# 05_RK3128_VDD.net
KiCad netlist of a schematic drawn in Altium Designer
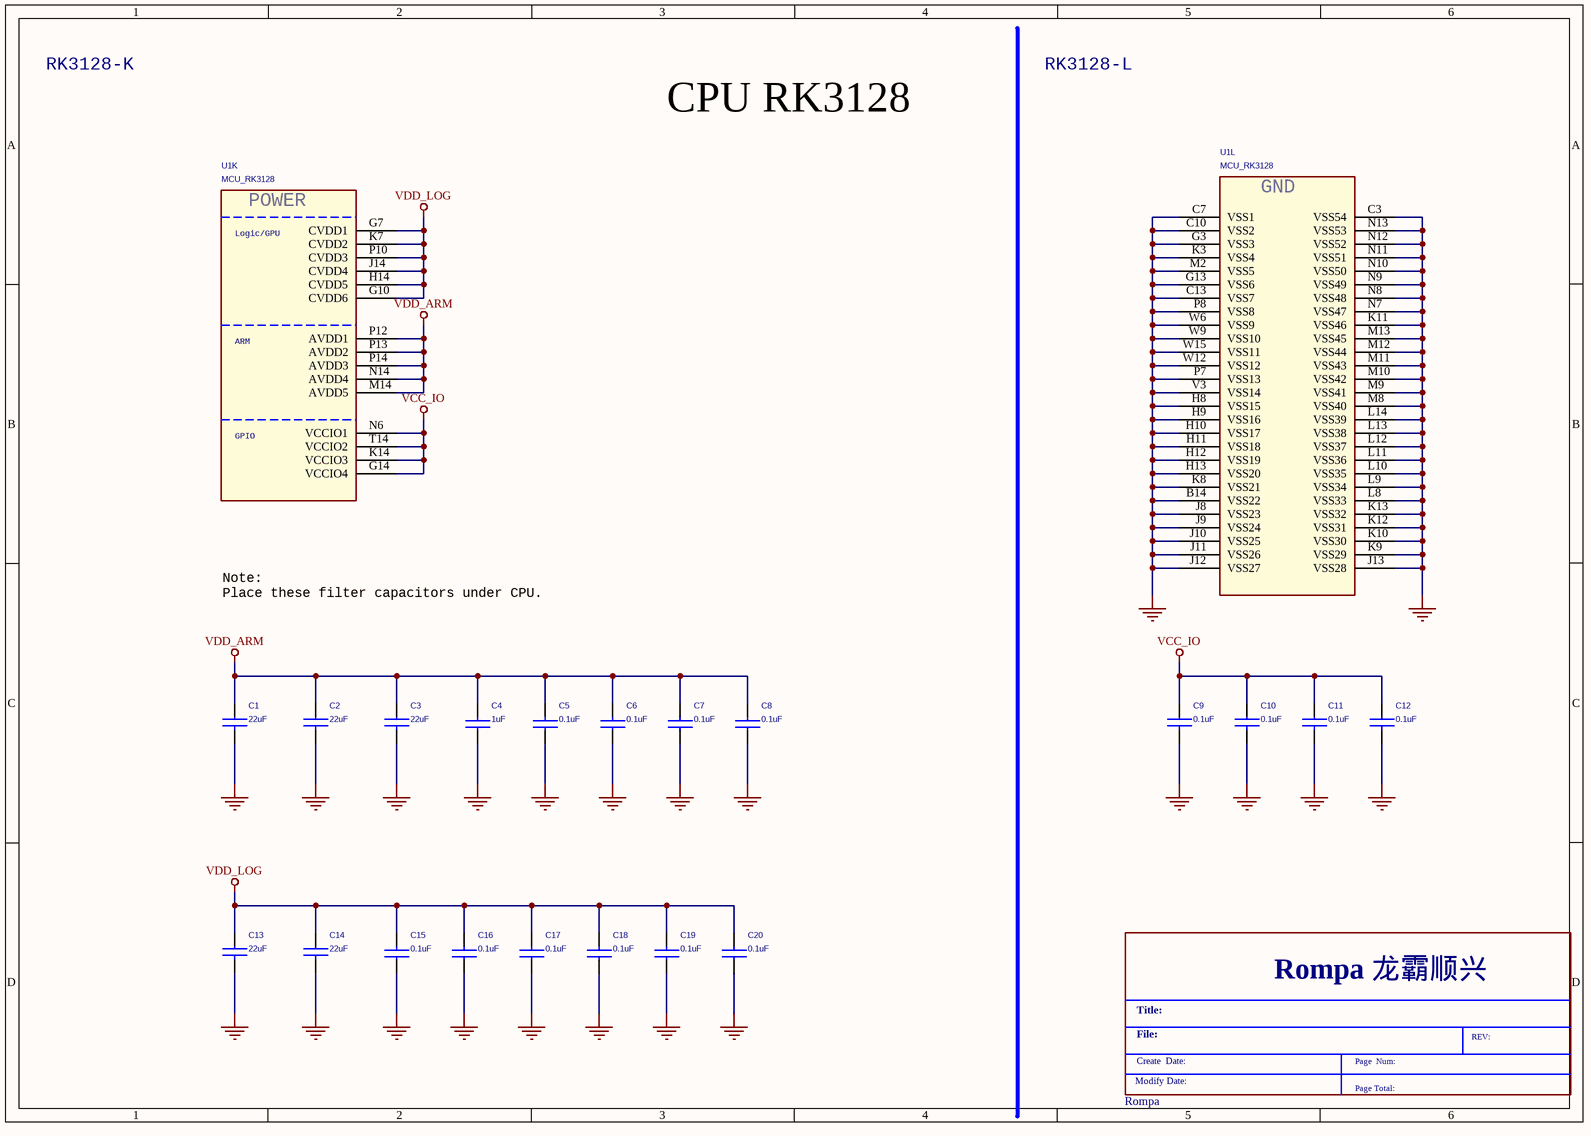
[diagram p0: 05_RK3128_VDD.SchDoc]

(export (version "E")
  (design (tool "Eeschema 10.0.6"))
  (components
    (comp (ref "C1")
      (value "22uF")
      (footprint "C0805")
      (description "RoHS CHIP CAP 22uF +10/-10% X5R")
      (libsource (lib "*") (part "CAP NP"))
    )
    (comp (ref "C2")
      (value "22uF")
      (footprint "C0805")
      (description "RoHS CHIP CAP 22uF +10/-10% X5R")
      (libsource (lib "*") (part "CAP NP"))
    )
    (comp (ref "C3")
      (value "22uF")
      (footprint "C0805")
      (description "RoHS CHIP CAP 22uF +10/-10% X5R")
      (libsource (lib "*") (part "CAP NP"))
    )
    (comp (ref "C4")
      (value "1uF")
      (footprint "C0402")
      (description "RoHS CHIP CAP 1uF +10/-10% X5R")
      (libsource (lib "*") (part "CAP NP"))
    )
    (comp (ref "C5")
      (value "0.1uF")
      (footprint "C0402")
      (description "RoHS CHIP CAP 0.1uF +10/-10% X7R")
      (libsource (lib "*") (part "CAP NP"))
    )
    (comp (ref "C6")
      (value "0.1uF")
      (footprint "C0402")
      (description "RoHS CHIP CAP 0.1uF +10/-10% X7R")
      (libsource (lib "*") (part "CAP NP"))
    )
    (comp (ref "C7")
      (value "0.1uF")
      (footprint "C0402")
      (description "RoHS CHIP CAP 0.1uF +10/-10% X7R")
      (libsource (lib "*") (part "CAP NP"))
    )
    (comp (ref "C8")
      (value "0.1uF")
      (footprint "C0402")
      (description "RoHS CHIP CAP 0.1uF +10/-10% X7R")
      (libsource (lib "*") (part "CAP NP"))
    )
    (comp (ref "C9")
      (value "0.1uF")
      (footprint "C0402")
      (description "RoHS CHIP CAP 0.1uF +10/-10% X7R")
      (libsource (lib "*") (part "CAP NP"))
    )
    (comp (ref "C10")
      (value "0.1uF")
      (footprint "C0402")
      (description "RoHS CHIP CAP 0.1uF +10/-10% X7R")
      (libsource (lib "*") (part "CAP NP"))
    )
    (comp (ref "C11")
      (value "0.1uF")
      (footprint "C0402")
      (description "RoHS CHIP CAP 0.1uF +10/-10% X7R")
      (libsource (lib "*") (part "CAP NP"))
    )
    (comp (ref "C12")
      (value "0.1uF")
      (footprint "C0402")
      (description "RoHS CHIP CAP 0.1uF +10/-10% X7R")
      (libsource (lib "*") (part "CAP NP"))
    )
    (comp (ref "C13")
      (value "22uF")
      (footprint "C0805")
      (description "RoHS CHIP CAP 22uF +10/-10% X5R")
      (libsource (lib "*") (part "CAP NP"))
    )
    (comp (ref "C14")
      (value "22uF")
      (footprint "C0805")
      (description "RoHS CHIP CAP 22uF +10/-10% X5R")
      (libsource (lib "*") (part "CAP NP"))
    )
    (comp (ref "C15")
      (value "0.1uF")
      (footprint "C0402")
      (description "RoHS CHIP CAP 0.1uF +10/-10% X7R")
      (libsource (lib "*") (part "CAP NP"))
    )
    (comp (ref "C16")
      (value "0.1uF")
      (footprint "C0402")
      (description "RoHS CHIP CAP 0.1uF +10/-10% X7R")
      (libsource (lib "*") (part "CAP NP"))
    )
    (comp (ref "C17")
      (value "0.1uF")
      (footprint "C0402")
      (description "RoHS CHIP CAP 0.1uF +10/-10% X7R")
      (libsource (lib "*") (part "CAP NP"))
    )
    (comp (ref "C18")
      (value "0.1uF")
      (footprint "C0402")
      (description "RoHS CHIP CAP 0.1uF +10/-10% X7R")
      (libsource (lib "*") (part "CAP NP"))
    )
    (comp (ref "C19")
      (value "0.1uF")
      (footprint "C0402")
      (description "RoHS CHIP CAP 0.1uF +10/-10% X7R")
      (libsource (lib "*") (part "CAP NP"))
    )
    (comp (ref "C20")
      (value "0.1uF")
      (footprint "C0402")
      (description "RoHS CHIP CAP 0.1uF +10/-10% X7R")
      (libsource (lib "*") (part "CAP NP"))
    )
    (comp (ref "U1")
      (value "MCU_RK3128")
      (footprint "BGA316-14X14-0.65")
      (libsource (lib "*") (part "MCU_RK3128"))
    )
  )
  (nets
    (net (code "1") (name "GND") (class "Default")
      (node (ref "C1") (pin "2") (pinfunction "2_2") (pintype "passive"))
      (node (ref "C10") (pin "2") (pinfunction "2_2") (pintype "passive"))
      (node (ref "C11") (pin "2") (pinfunction "2_2") (pintype "passive"))
      (node (ref "C12") (pin "2") (pinfunction "2_2") (pintype "passive"))
      (node (ref "C13") (pin "2") (pinfunction "2_2") (pintype "passive"))
      (node (ref "C14") (pin "2") (pinfunction "2_2") (pintype "passive"))
      (node (ref "C15") (pin "1") (pinfunction "1_1") (pintype "passive"))
      (node (ref "C16") (pin "1") (pinfunction "1_1") (pintype "passive"))
      (node (ref "C17") (pin "1") (pinfunction "1_1") (pintype "passive"))
      (node (ref "C18") (pin "1") (pinfunction "1_1") (pintype "passive"))
      (node (ref "C19") (pin "1") (pinfunction "1_1") (pintype "passive"))
      (node (ref "C2") (pin "2") (pinfunction "2_2") (pintype "passive"))
      (node (ref "C20") (pin "1") (pinfunction "1_1") (pintype "passive"))
      (node (ref "C3") (pin "2") (pinfunction "2_2") (pintype "passive"))
      (node (ref "C4") (pin "1") (pinfunction "1_1") (pintype "passive"))
      (node (ref "C5") (pin "1") (pinfunction "1_1") (pintype "passive"))
      (node (ref "C6") (pin "1") (pinfunction "1_1") (pintype "passive"))
      (node (ref "C7") (pin "1") (pinfunction "1_1") (pintype "passive"))
      (node (ref "C8") (pin "1") (pinfunction "1_1") (pintype "passive"))
      (node (ref "C9") (pin "2") (pinfunction "2_2") (pintype "passive"))
      (node (ref "U1") (pin "B14") (pinfunction "VSS22_B14") (pintype "passive"))
      (node (ref "U1") (pin "C10") (pinfunction "VSS2_C10") (pintype "passive"))
      (node (ref "U1") (pin "C13") (pinfunction "VSS7_C13") (pintype "passive"))
      (node (ref "U1") (pin "C3") (pinfunction "VSS54_C3") (pintype "passive"))
      (node (ref "U1") (pin "C7") (pinfunction "VSS1_C7") (pintype "passive"))
      (node (ref "U1") (pin "G13") (pinfunction "VSS6_G13") (pintype "passive"))
      (node (ref "U1") (pin "G3") (pinfunction "VSS3_G3") (pintype "passive"))
      (node (ref "U1") (pin "H10") (pinfunction "VSS17_H10") (pintype "passive"))
      (node (ref "U1") (pin "H11") (pinfunction "VSS18_H11") (pintype "passive"))
      (node (ref "U1") (pin "H12") (pinfunction "VSS19_H12") (pintype "passive"))
      (node (ref "U1") (pin "H13") (pinfunction "VSS20_H13") (pintype "passive"))
      (node (ref "U1") (pin "H8") (pinfunction "VSS15_H8") (pintype "passive"))
      (node (ref "U1") (pin "H9") (pinfunction "VSS16_H9") (pintype "passive"))
      (node (ref "U1") (pin "J10") (pinfunction "VSS25_J10") (pintype "passive"))
      (node (ref "U1") (pin "J11") (pinfunction "VSS26_J11") (pintype "passive"))
      (node (ref "U1") (pin "J12") (pinfunction "VSS27_J12") (pintype "passive"))
      (node (ref "U1") (pin "J13") (pinfunction "VSS28_J13") (pintype "passive"))
      (node (ref "U1") (pin "J8") (pinfunction "VSS23_J8") (pintype "passive"))
      (node (ref "U1") (pin "J9") (pinfunction "VSS24_J9") (pintype "passive"))
      (node (ref "U1") (pin "K10") (pinfunction "VSS30_K10") (pintype "passive"))
      (node (ref "U1") (pin "K11") (pinfunction "VSS46_K11") (pintype "passive"))
      (node (ref "U1") (pin "K12") (pinfunction "VSS31_K12") (pintype "passive"))
      (node (ref "U1") (pin "K13") (pinfunction "VSS32_K13") (pintype "passive"))
      (node (ref "U1") (pin "K3") (pinfunction "VSS4_K3") (pintype "passive"))
      (node (ref "U1") (pin "K8") (pinfunction "VSS21_K8") (pintype "passive"))
      (node (ref "U1") (pin "K9") (pinfunction "VSS29_K9") (pintype "passive"))
      (node (ref "U1") (pin "L10") (pinfunction "VSS35_L10") (pintype "passive"))
      (node (ref "U1") (pin "L11") (pinfunction "VSS36_L11") (pintype "passive"))
      (node (ref "U1") (pin "L12") (pinfunction "VSS37_L12") (pintype "passive"))
      (node (ref "U1") (pin "L13") (pinfunction "VSS38_L13") (pintype "passive"))
      (node (ref "U1") (pin "L14") (pinfunction "VSS39_L14") (pintype "passive"))
      (node (ref "U1") (pin "L8") (pinfunction "VSS33_L8") (pintype "passive"))
      (node (ref "U1") (pin "L9") (pinfunction "VSS34_L9") (pintype "passive"))
      (node (ref "U1") (pin "M10") (pinfunction "VSS42_M10") (pintype "passive"))
      (node (ref "U1") (pin "M11") (pinfunction "VSS43_M11") (pintype "passive"))
      (node (ref "U1") (pin "M12") (pinfunction "VSS44_M12") (pintype "passive"))
      (node (ref "U1") (pin "M13") (pinfunction "VSS45_M13") (pintype "passive"))
      (node (ref "U1") (pin "M2") (pinfunction "VSS5_M2") (pintype "passive"))
      (node (ref "U1") (pin "M8") (pinfunction "VSS40_M8") (pintype "passive"))
      (node (ref "U1") (pin "M9") (pinfunction "VSS41_M9") (pintype "passive"))
      (node (ref "U1") (pin "N10") (pinfunction "VSS50_N10") (pintype "passive"))
      (node (ref "U1") (pin "N11") (pinfunction "VSS51_N11") (pintype "passive"))
      (node (ref "U1") (pin "N12") (pinfunction "VSS52_N12") (pintype "passive"))
      (node (ref "U1") (pin "N13") (pinfunction "VSS53_N13") (pintype "passive"))
      (node (ref "U1") (pin "N7") (pinfunction "VSS47_N7") (pintype "passive"))
      (node (ref "U1") (pin "N8") (pinfunction "VSS48_N8") (pintype "passive"))
      (node (ref "U1") (pin "N9") (pinfunction "VSS49_N9") (pintype "passive"))
      (node (ref "U1") (pin "P7") (pinfunction "VSS13_P7") (pintype "passive"))
      (node (ref "U1") (pin "P8") (pinfunction "VSS8_P8") (pintype "passive"))
      (node (ref "U1") (pin "V3") (pinfunction "VSS14_V3") (pintype "passive"))
      (node (ref "U1") (pin "W12") (pinfunction "VSS12_W12") (pintype "passive"))
      (node (ref "U1") (pin "W15") (pinfunction "VSS11_W15") (pintype "passive"))
      (node (ref "U1") (pin "W6") (pinfunction "VSS9_W6") (pintype "passive"))
      (node (ref "U1") (pin "W9") (pinfunction "VSS10_W9") (pintype "passive"))
    )
    (net (code "2") (name "VCC_IO") (class "Default")
      (node (ref "C10") (pin "1") (pinfunction "1_1") (pintype "passive"))
      (node (ref "C11") (pin "1") (pinfunction "1_1") (pintype "passive"))
      (node (ref "C12") (pin "1") (pinfunction "1_1") (pintype "passive"))
      (node (ref "C9") (pin "1") (pinfunction "1_1") (pintype "passive"))
      (node (ref "U1") (pin "G14") (pinfunction "VCCIO4_G14") (pintype "passive"))
      (node (ref "U1") (pin "K14") (pinfunction "VCCIO3_K14") (pintype "passive"))
      (node (ref "U1") (pin "N6") (pinfunction "VCCIO1_N6") (pintype "passive"))
      (node (ref "U1") (pin "T14") (pinfunction "VCCIO2_T14") (pintype "passive"))
    )
    (net (code "3") (name "VDD_ARM") (class "Default")
      (node (ref "C1") (pin "1") (pinfunction "1_1") (pintype "passive"))
      (node (ref "C2") (pin "1") (pinfunction "1_1") (pintype "passive"))
      (node (ref "C3") (pin "1") (pinfunction "1_1") (pintype "passive"))
      (node (ref "C4") (pin "2") (pinfunction "2_2") (pintype "passive"))
      (node (ref "C5") (pin "2") (pinfunction "2_2") (pintype "passive"))
      (node (ref "C6") (pin "2") (pinfunction "2_2") (pintype "passive"))
      (node (ref "C7") (pin "2") (pinfunction "2_2") (pintype "passive"))
      (node (ref "C8") (pin "2") (pinfunction "2_2") (pintype "passive"))
      (node (ref "U1") (pin "M14") (pinfunction "AVDD5_M14") (pintype "passive"))
      (node (ref "U1") (pin "N14") (pinfunction "AVDD4_N14") (pintype "passive"))
      (node (ref "U1") (pin "P12") (pinfunction "AVDD1_P12") (pintype "passive"))
      (node (ref "U1") (pin "P13") (pinfunction "AVDD2_P13") (pintype "passive"))
      (node (ref "U1") (pin "P14") (pinfunction "AVDD3_P14") (pintype "passive"))
    )
    (net (code "4") (name "VDD_LOG") (class "Default")
      (node (ref "C13") (pin "1") (pinfunction "1_1") (pintype "passive"))
      (node (ref "C14") (pin "1") (pinfunction "1_1") (pintype "passive"))
      (node (ref "C15") (pin "2") (pinfunction "2_2") (pintype "passive"))
      (node (ref "C16") (pin "2") (pinfunction "2_2") (pintype "passive"))
      (node (ref "C17") (pin "2") (pinfunction "2_2") (pintype "passive"))
      (node (ref "C18") (pin "2") (pinfunction "2_2") (pintype "passive"))
      (node (ref "C19") (pin "2") (pinfunction "2_2") (pintype "passive"))
      (node (ref "C20") (pin "2") (pinfunction "2_2") (pintype "passive"))
      (node (ref "U1") (pin "G10") (pinfunction "CVDD6_G10") (pintype "passive"))
      (node (ref "U1") (pin "G7") (pinfunction "CVDD1_G7") (pintype "passive"))
      (node (ref "U1") (pin "H14") (pinfunction "CVDD5_H14") (pintype "passive"))
      (node (ref "U1") (pin "J14") (pinfunction "CVDD4_J14") (pintype "passive"))
      (node (ref "U1") (pin "K7") (pinfunction "CVDD2_K7") (pintype "passive"))
      (node (ref "U1") (pin "P10") (pinfunction "CVDD3_P10") (pintype "passive"))
    )
  )
)
